# amplifier.net
KiCad netlist of a schematic drawn in Altium Designer
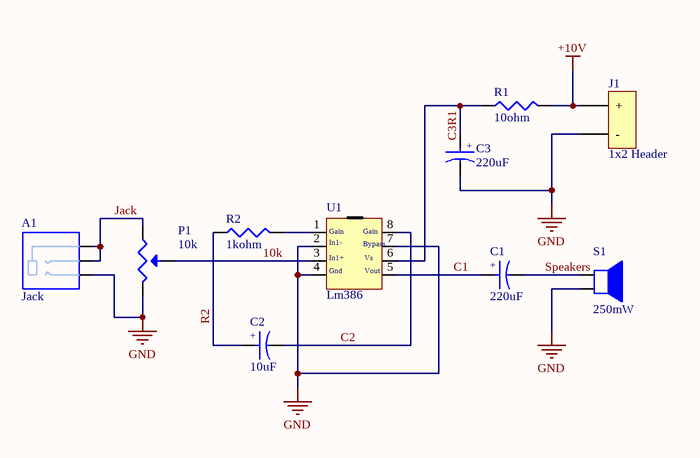
[diagram p0: amplifier.SchDoc]

(export (version "E")
  (design (tool "Eeschema 10.0.6"))
  (components
    (comp (ref "A1")
      (value "Jack")
      (footprint "SJ252")
      (description "2.50mm (0.094\", 3/32\", Sub Mini, Miniature) - Headphone Phone Jack Stereo Connector Solder")
      (fields (field (name "MANUFACTURER") "CUI") (field (name "MANUFACTURER PART NUMBER") "SJ-2523-SMT-TR"))
      (libsource (lib "amplifier") (part "SJ-2523-SMT-TR"))
    )
    (comp (ref "C1")
      (value "220uF")
      (footprint "C6SVPE")
      (description "Cap Aluminum Polymer 220uF 6.3VDC 20% (5 X 5.9mm) SMD 0.015 Ohm 3150mA 2000h 105C T/R")
      (fields
        (field (name "MANUFACTURER") "Panasonic")
        (field (name "MANUFACTURER PART NUMBER") "6SVPE220MW")
      )
      (libsource (lib "amplifier") (part "6SVPE220MW"))
    )
    (comp (ref "C2")
      (value "10uF")
      (footprint "C10SVP")
      (description "CAP POLYMER 10UF 20% 10V SMD")
      (fields (field (name "MANUFACTURER") "Panasonic") (field (name "MANUFACTURER PART NUMBER") "10SVP10M"))
      (libsource (lib "amplifier") (part "10SVP10M"))
    )
    (comp (ref "C3")
      (value "220uF")
      (footprint "C6SVPE")
      (description "Cap Aluminum Polymer 220uF 6.3VDC 20% (5 X 5.9mm) SMD 0.015 Ohm 3150mA 2000h 105C T/R")
      (fields
        (field (name "MANUFACTURER") "Panasonic")
        (field (name "MANUFACTURER PART NUMBER") "6SVPE220MW")
      )
      (libsource (lib "amplifier") (part "6SVPE220MW"))
    )
    (comp (ref "J1")
      (value "1x2 Header")
      (footprint "HDR1x2")
      (description "Headers & Wire Housings 2 PIN F/LK HEADER")
      (fields (field (name "MANUFACTURER") "Molex") (field (name "MANUFACTURER PART NUMBER") "22-29-2021"))
      (libsource (lib "amplifier") (part "22-29-2021"))
    )
    (comp (ref "P1")
      (value "10k")
      (footprint "91A1A")
      (fields
        (field (name "MANUFACTURER") "Bourns")
        (field (name "MANUFACTURER PART NUMBER") "91A1A-B28-B15L")
        (field (name "TOLERANCE") "20%")
      )
      (libsource (lib "amplifier") (part "91A1A-B28-B15L"))
    )
    (comp (ref "R1")
      (value "10ohm")
      (footprint "R0402")
      (description "Thick Film Resistors 0.2W 10ohms 1% High Power AEC-Q200")
      (fields
        (field (name "MANUFACTURER") "Vishay Dale")
        (field (name "MANUFACTURER PART NUMBER") "CRCW040210R0FKEDHP")
      )
      (libsource (lib "amplifier") (part "CRCW040210R0FKEDHP"))
    )
    (comp (ref "R2")
      (value "1kohm")
      (footprint "R0603")
      (description "Thin Film Resistors - SMD 1/10watt 1Kohms 0.1% 5ppm")
      (fields
        (field (name "MANUFACTURER") "Vishay Dale")
        (field (name "MANUFACTURER PART NUMBER") "TNPU06031K00BZEN00")
      )
      (libsource (lib "amplifier") (part "TNPU06031K00BZEN00"))
    )
    (comp (ref "S1")
      (value "250mW")
      (footprint "CLF038")
      (description "8 Ohm Magnetic Speaker 250mW 380Hz ~ 10kHz Top Round 93dB")
      (fields (field (name "MANUFACTURER") "CUI") (field (name "MANUFACTURER PART NUMBER") "CLF0381MP-1"))
      (libsource (lib "amplifier") (part "CLF0381MP-1"))
    )
    (comp (ref "U1")
      (value "Lm386")
      (footprint "LM386MX")
      (description "TEXAS INSTRUMENTS   LM386MX-1/NOPB   AUDIO POWER AMPLIFIER, CLASS AB 325mW SOIC-8")
      (fields
        (field (name "MANUFACTURER") "TI National Semiconductor")
        (field (name "MANUFACTURER PART NUMBER") "LM386MX-1/NOPB")
      )
      (libsource (lib "amplifier") (part "LM386MX-1/NOPB"))
    )
  )
  (nets
    (net (code "1") (name "+10V") (class "Default")
      (node (ref "J1") (pin "1") (pinfunction "+_1") (pintype "passive"))
      (node (ref "R1") (pin "2") (pinfunction "2_2") (pintype "passive"))
    )
    (net (code "2") (name "/10k") (class "Default")
      (node (ref "P1") (pin "3") (pinfunction "3_3") (pintype "passive"))
      (node (ref "U1") (pin "3") (pinfunction "3_3") (pintype "passive"))
    )
    (net (code "3") (name "/C1") (class "Default")
      (node (ref "C1") (pin "1") (pinfunction "1_1") (pintype "passive"))
      (node (ref "U1") (pin "5") (pinfunction "5_5") (pintype "passive"))
    )
    (net (code "4") (name "/C2") (class "Default")
      (node (ref "C2") (pin "2") (pinfunction "2_2") (pintype "passive"))
      (node (ref "U1") (pin "8") (pinfunction "8_8") (pintype "passive"))
    )
    (net (code "6") (name "/Jack") (class "Default")
      (node (ref "A1") (pin "1") (pinfunction "1_1") (pintype "passive"))
      (node (ref "A1") (pin "2") (pinfunction "2_2") (pintype "passive"))
      (node (ref "P1") (pin "1") (pinfunction "1_1") (pintype "passive"))
    )
    (net (code "7") (name "/R2") (class "Default")
      (node (ref "C2") (pin "1") (pinfunction "1_1") (pintype "passive"))
      (node (ref "R2") (pin "1") (pinfunction "1_1") (pintype "passive"))
    )
    (net (code "8") (name "/Speakers") (class "Default")
      (node (ref "C1") (pin "2") (pinfunction "2_2") (pintype "passive"))
      (node (ref "S1") (pin "1") (pinfunction "1_1") (pintype "passive"))
    )
    (net (code "9") (name "GND") (class "Default")
      (node (ref "A1") (pin "3") (pinfunction "3_3") (pintype "passive"))
      (node (ref "C3") (pin "2") (pinfunction "2_2") (pintype "passive"))
      (node (ref "J1") (pin "2") (pinfunction "-_2") (pintype "passive"))
      (node (ref "P1") (pin "2") (pinfunction "2_2") (pintype "passive"))
      (node (ref "S1") (pin "2") (pinfunction "2_2") (pintype "passive"))
      (node (ref "U1") (pin "2") (pinfunction "2_2") (pintype "passive"))
      (node (ref "U1") (pin "4") (pinfunction "4_4") (pintype "passive"))
      (node (ref "U1") (pin "7") (pinfunction "7_7") (pintype "passive"))
    )
    (net (code "10") (name "Net-(C3-Pad1)") (class "Default")
      (node (ref "C3") (pin "1") (pinfunction "1_1") (pintype "passive"))
      (node (ref "R1") (pin "1") (pinfunction "1_1") (pintype "passive"))
      (node (ref "U1") (pin "6") (pinfunction "6_6") (pintype "passive"))
    )
    (net (code "11") (name "Net-(R2-Pad2)") (class "Default")
      (node (ref "R2") (pin "2") (pinfunction "2_2") (pintype "passive"))
      (node (ref "U1") (pin "1") (pinfunction "1_1") (pintype "passive"))
    )
  )
)
